# signal.net
KiCad netlist of a schematic drawn in Altium Designer
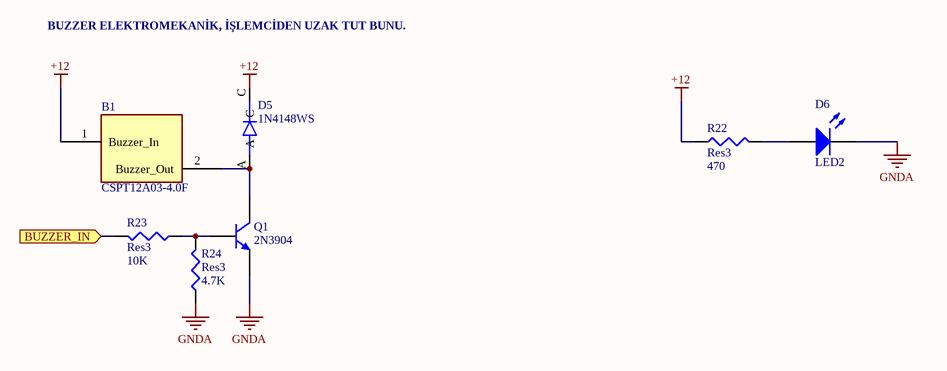
[diagram p0: signal.SchDoc]

(export (version "E")
  (design (tool "Eeschema 10.0.6"))
  (components
    (comp (ref "B1")
      (value "CSPT12A03-4.0F")
      (footprint "Buzzer SMD")
      (description "12V 1mA 5MM 85dB 7.5X7.5X2 SMD Buzzer without circuit")
      (libsource (lib "RoketAnaSistemSematikKütüphane") (part "Buzzer SMD 5MM"))
    )
    (comp (ref "D5")
      (value "1N4148WS")
      (footprint "1N4148WS")
      (description "Diode Standard 75V 150mA Surface Mount SOD-323F")
      (fields (field (name "MF") "ON Semiconductor"))
      (libsource (lib "RoketAnaSistemSematikKütüphane") (part "1N4148WS"))
    )
    (comp (ref "D6")
      (value "LED2")
      (footprint "3.2X1.6X1.1")
      (description "Typical RED, GREEN, YELLOW, AMBER GaAs LED")
      (fields (field (name "PUBLISHER") "Altium Limited"))
      (libsource (lib "Miscellaneous Devices") (part "LED2"))
    )
    (comp (ref "Q1")
      (value "2N3904")
      (footprint "TO-92A")
      (description "NPN General Purpose Amplifier")
      (fields (field (name "PUBLISHER") "Altium Limited"))
      (libsource (lib "Miscellaneous Devices") (part "2N3904"))
    )
    (comp (ref "R22")
      (value "Res3")
      (footprint "12Z-2010")
      (description "Resistor")
      (fields (field (name "ALTIUM_VALUE") "470") (field (name "PUBLISHER") "Altium Limited"))
      (libsource (lib "Miscellaneous Devices") (part "Res3"))
    )
    (comp (ref "R23")
      (value "Res3")
      (footprint "J1-0603")
      (description "Resistor")
      (fields (field (name "ALTIUM_VALUE") "10K") (field (name "PUBLISHER") "Altium Limited"))
      (libsource (lib "Miscellaneous Devices") (part "Res3"))
    )
    (comp (ref "R24")
      (value "Res3")
      (footprint "J1-0603")
      (description "Resistor")
      (fields (field (name "ALTIUM_VALUE") "4.7K") (field (name "PUBLISHER") "Altium Limited"))
      (libsource (lib "Miscellaneous Devices") (part "Res3"))
    )
  )
  (nets
    (net (code "1") (name "+12") (class "Default")
      (node (ref "B1") (pin "1") (pinfunction "Buzzer_In_1") (pintype "passive"))
      (node (ref "D5") (pin "C") (pinfunction "C_C") (pintype "passive"))
      (node (ref "R22") (pin "1") (pinfunction "1_1") (pintype "passive"))
    )
    (net (code "2") (name "/BUZZER_IN") (class "Default")
      (node (ref "R23") (pin "2") (pinfunction "2_2") (pintype "passive"))
    )
    (net (code "3") (name "GNDA") (class "Default")
      (node (ref "D6") (pin "2") (pinfunction "K_2") (pintype "passive"))
      (node (ref "Q1") (pin "1") (pinfunction "E_1") (pintype "passive"))
      (node (ref "R24") (pin "1") (pinfunction "1_1") (pintype "passive"))
    )
    (net (code "4") (name "Net-(B1-Buzzer_Out)") (class "Default")
      (node (ref "B1") (pin "2") (pinfunction "Buzzer_Out_2") (pintype "passive"))
      (node (ref "D5") (pin "A") (pinfunction "A_A") (pintype "passive"))
      (node (ref "Q1") (pin "3") (pinfunction "C_3") (pintype "passive"))
    )
    (net (code "5") (name "Net-(D6-A)") (class "Default")
      (node (ref "D6") (pin "1") (pinfunction "A_1") (pintype "passive"))
      (node (ref "R22") (pin "2") (pinfunction "2_2") (pintype "passive"))
    )
    (net (code "6") (name "Net-(Q1-B)") (class "Default")
      (node (ref "Q1") (pin "2") (pinfunction "B_2") (pintype "passive"))
      (node (ref "R23") (pin "1") (pinfunction "1_1") (pintype "passive"))
      (node (ref "R24") (pin "2") (pinfunction "2_2") (pintype "passive"))
    )
  )
)
